# TC264Main.net
KiCad netlist of a schematic drawn in Altium Designer
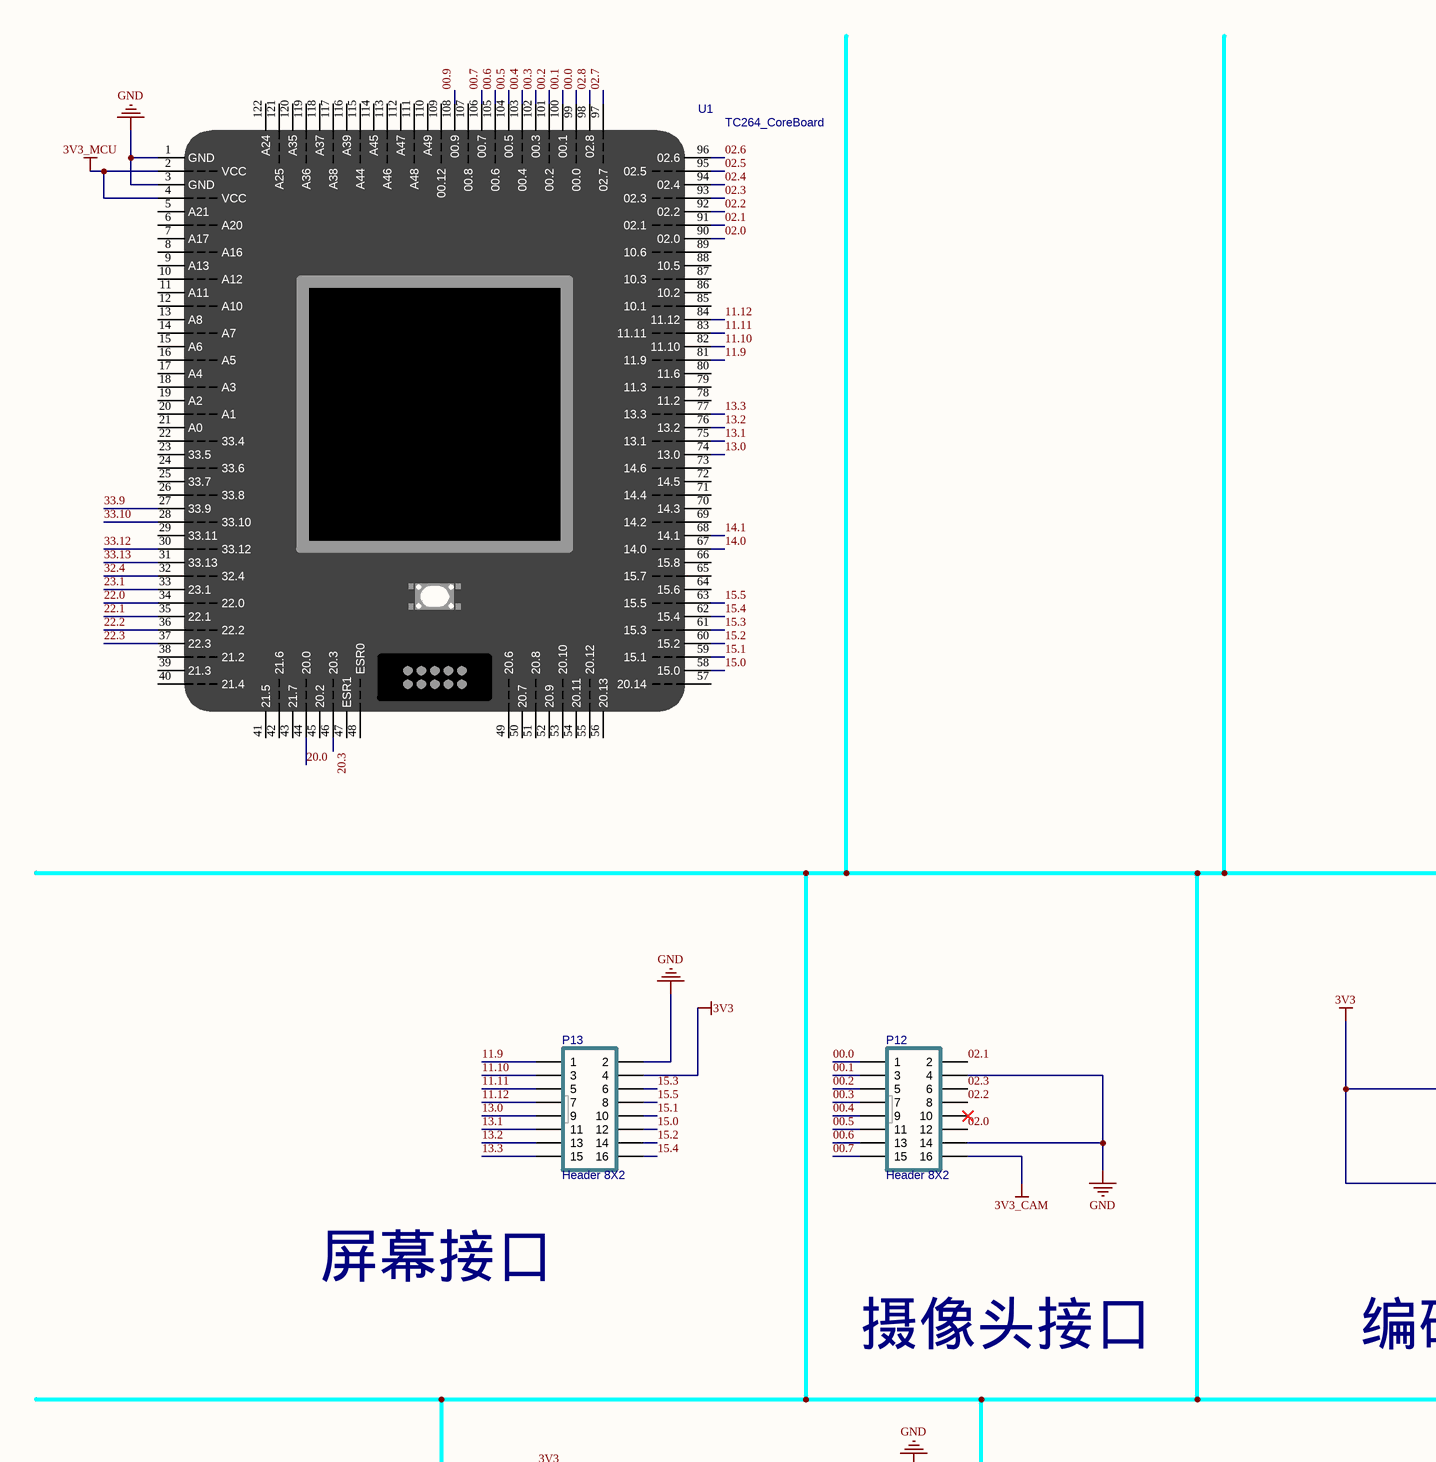
[diagram p0: TC264Main.SchDoc, top left]
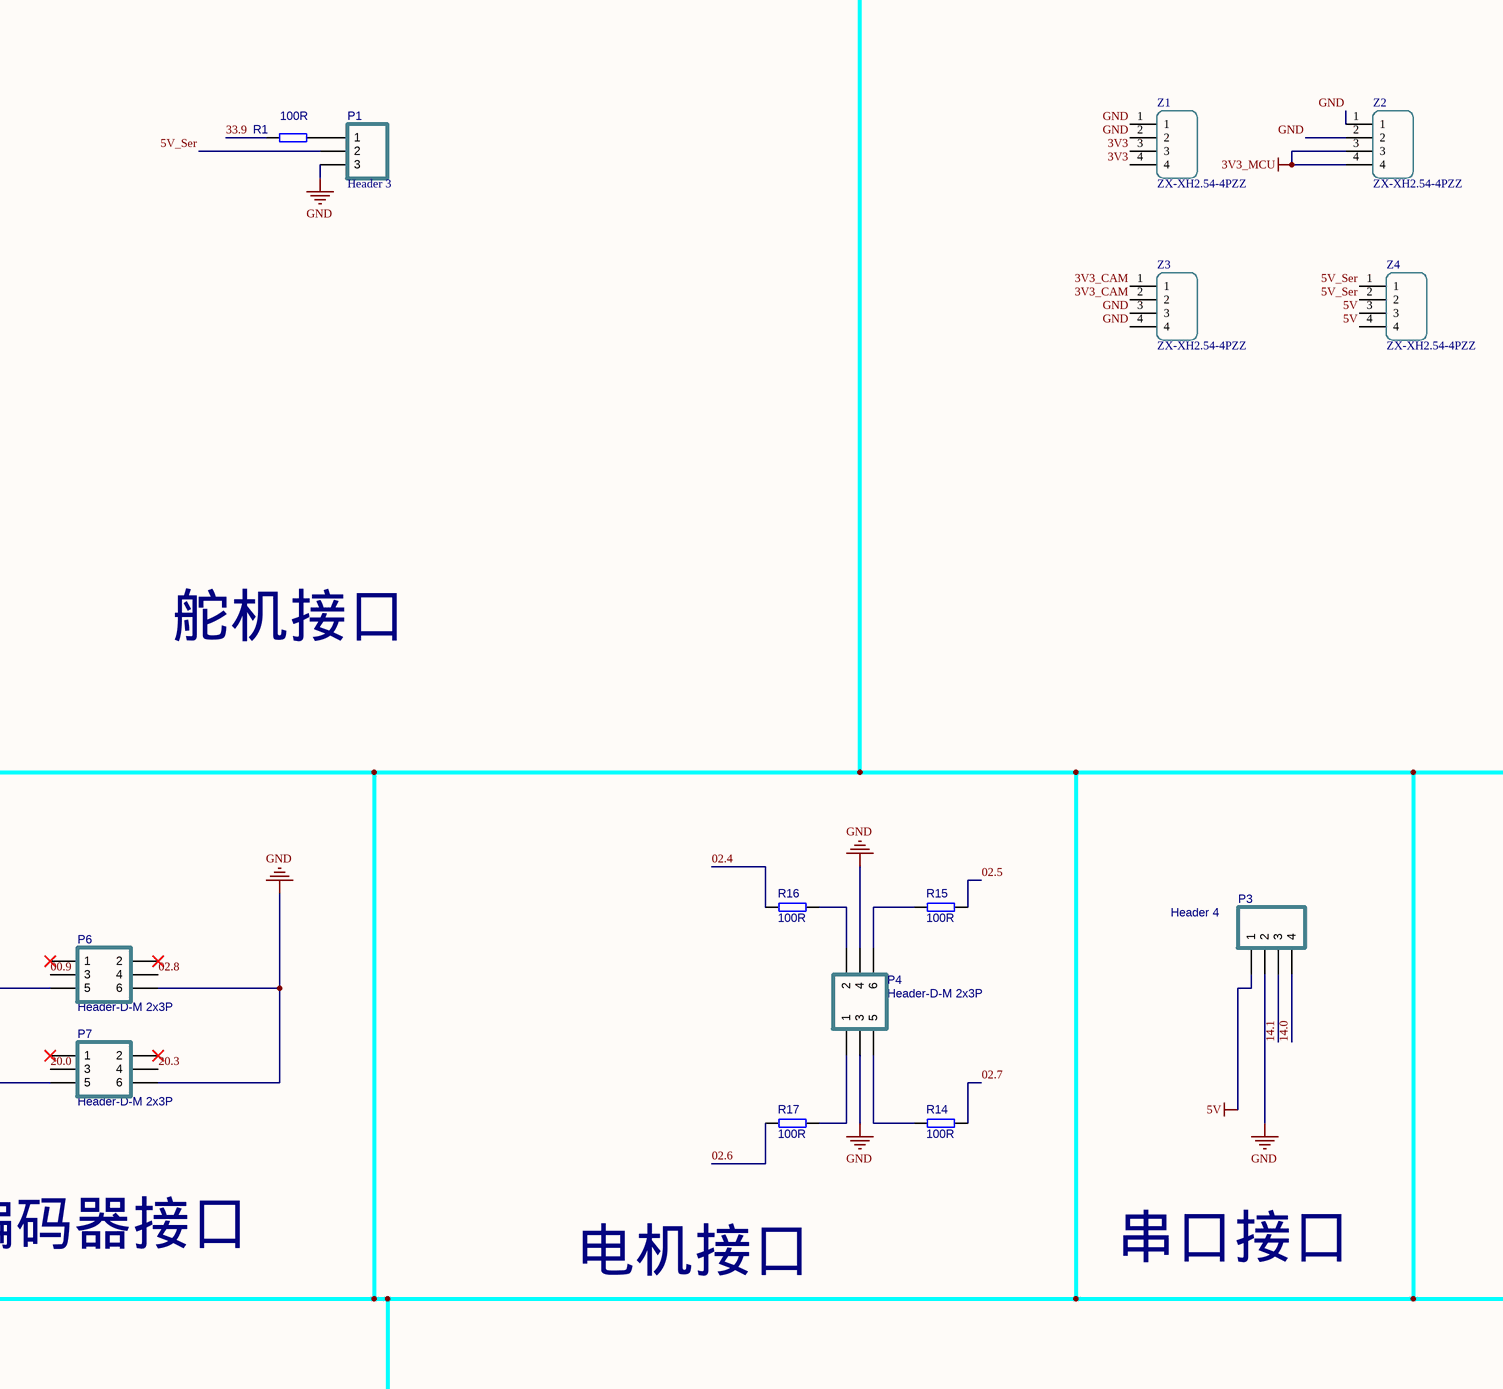
[diagram p1: TC264Main.SchDoc, top middle]
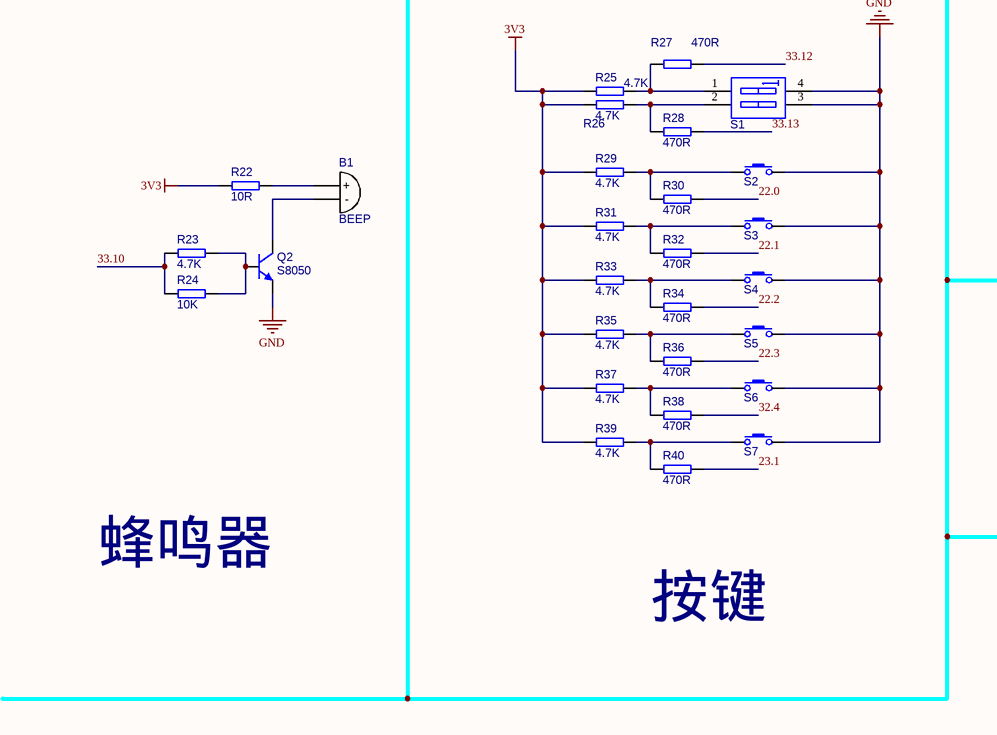
[diagram p2: TC264Main.SchDoc, bottom left]

(export (version "E")
  (design (tool "Eeschema 10.0.6"))
  (components
    (comp (ref "B1")
      (value "BEEP")
      (footprint "BEEP 9x5.5mm")
      (description "蜂鸣器")
      (libsource (lib "TC264") (part "BEEP"))
    )
    (comp (ref "P1")
      (value "Header 3")
      (footprint "HDR1X3")
      (description "Header, 3-Pin")
      (fields (field (name "PUBLISHER") "Altium Limited"))
      (libsource (lib "TC264") (part "Header 3"))
    )
    (comp (ref "P3")
      (value "Header 4")
      (footprint "HDR1X4")
      (description "Header, 4-Pin")
      (fields (field (name "PUBLISHER") "Altium Limited"))
      (libsource (lib "TC264") (part "Header 4"))
    )
    (comp (ref "P4")
      (value "Header-D-M 2x3P")
      (footprint "HDR2X3-M")
      (description "2x3pin, 直插, 双排针")
      (libsource (lib "") (part "Header-D-M 2x3P_1"))
    )
    (comp (ref "P6")
      (value "Header-D-M 2x3P")
      (footprint "HDR2X3-M")
      (description "2x3pin, 直插, 双排针")
      (libsource (lib "TC264") (part "Header-D-M 2x3P"))
    )
    (comp (ref "P7")
      (value "Header-D-M 2x3P")
      (footprint "HDR2X3-M")
      (description "2x3pin, 直插, 双排针")
      (libsource (lib "TC264") (part "Header-D-M 2x3P"))
    )
    (comp (ref "P12")
      (value "Header 8X2")
      (footprint "HDR2X8")
      (description "Header, 8-Pin, Dual row")
      (fields (field (name "PUBLISHER") "Altium Limited"))
      (libsource (lib "TC264") (part "Header 8X2"))
    )
    (comp (ref "P13")
      (value "Header 8X2")
      (footprint "HDR2X8")
      (description "Header, 8-Pin, Dual row")
      (fields (field (name "PUBLISHER") "Altium Limited"))
      (libsource (lib "TC264") (part "Header 8X2"))
    )
    (comp (ref "Q2")
      (value "S8050")
      (footprint "SOT-23")
      (description "Discrete NPN Bipolar Transistor")
      (fields (field (name "PARTNUMBER") "S8050") (field (name "PUBLISHER") "Altium Limited"))
      (libsource (lib "TC264") (part "NPN S8050"))
    )
    (comp (ref "R1")
      (value "100R")
      (footprint "RESC1608[0603]S-N")
      (description "贴片电阻")
      (fields (field (name "TOLERANCE") "±1%") (field (name "Comment") "100R ±1%"))
      (libsource (lib "TC264") (part "Res-Chip_1"))
    )
    (comp (ref "R14")
      (value "100R")
      (footprint "RESC1608[0603]S-N")
      (description "贴片电阻")
      (fields (field (name "TOLERANCE") "±1%") (field (name "Comment") "100R ±1%"))
      (libsource (lib "TC264") (part "Res-Chip_1"))
    )
    (comp (ref "R15")
      (value "100R")
      (footprint "RESC1608[0603]S-N")
      (description "贴片电阻")
      (fields (field (name "TOLERANCE") "±1%") (field (name "Comment") "100R ±1%"))
      (libsource (lib "TC264") (part "Res-Chip_1"))
    )
    (comp (ref "R16")
      (value "100R")
      (footprint "RESC1608[0603]S-N")
      (description "贴片电阻")
      (fields (field (name "TOLERANCE") "±1%") (field (name "Comment") "100R ±1%"))
      (libsource (lib "TC264") (part "Res-Chip_1"))
    )
    (comp (ref "R17")
      (value "100R")
      (footprint "RESC1608[0603]S-N")
      (description "贴片电阻")
      (fields (field (name "TOLERANCE") "±1%") (field (name "Comment") "100R ±1%"))
      (libsource (lib "TC264") (part "Res-Chip_1"))
    )
    (comp (ref "R22")
      (value "10R")
      (footprint "RESC1608[0603]S-N")
      (description "贴片电阻")
      (fields (field (name "TOLERANCE") "±1%") (field (name "Comment") "10R ±1%"))
      (libsource (lib "TC264") (part "Res-Chip_10"))
    )
    (comp (ref "R23")
      (value "4.7K")
      (footprint "RESC1608[0603]S-N")
      (description "贴片电阻")
      (fields (field (name "TOLERANCE") "±1%") (field (name "Comment") "4.7K ±1%"))
      (libsource (lib "TC264") (part "Res-Chip_4"))
    )
    (comp (ref "R24")
      (value "10K")
      (footprint "RESC1608[0603]S-N")
      (description "贴片电阻")
      (fields (field (name "TOLERANCE") "±1%") (field (name "Comment") "10K ±1%"))
      (libsource (lib "TC264") (part "Res-Chip"))
    )
    (comp (ref "R25")
      (value "4.7K")
      (footprint "RESC1608[0603]S-N")
      (description "贴片电阻")
      (fields (field (name "TOLERANCE") "±1%") (field (name "Comment") "4.7K ±1%"))
      (libsource (lib "TC264") (part "Res-Chip_4"))
    )
    (comp (ref "R26")
      (value "4.7K")
      (footprint "RESC1608[0603]S-N")
      (description "贴片电阻")
      (fields (field (name "TOLERANCE") "±1%") (field (name "Comment") "4.7K ±1%"))
      (libsource (lib "TC264") (part "Res-Chip_4"))
    )
    (comp (ref "R27")
      (value "470R")
      (footprint "RESC1608[0603]S-N")
      (description "贴片电阻")
      (fields (field (name "TOLERANCE") "±1%") (field (name "Comment") "470R ±1%"))
      (libsource (lib "TC264") (part "Res-Chip_11"))
    )
    (comp (ref "R28")
      (value "470R")
      (footprint "RESC1608[0603]S-N")
      (description "贴片电阻")
      (fields (field (name "TOLERANCE") "±1%") (field (name "Comment") "470R ±1%"))
      (libsource (lib "TC264") (part "Res-Chip_11"))
    )
    (comp (ref "R29")
      (value "4.7K")
      (footprint "RESC1608[0603]S-N")
      (description "贴片电阻")
      (fields (field (name "TOLERANCE") "±1%") (field (name "Comment") "4.7K ±1%"))
      (libsource (lib "TC264") (part "Res-Chip_4"))
    )
    (comp (ref "R30")
      (value "470R")
      (footprint "RESC1608[0603]S-N")
      (description "贴片电阻")
      (fields (field (name "TOLERANCE") "±1%") (field (name "Comment") "470R ±1%"))
      (libsource (lib "TC264") (part "Res-Chip_11"))
    )
    (comp (ref "R31")
      (value "4.7K")
      (footprint "RESC1608[0603]S-N")
      (description "贴片电阻")
      (fields (field (name "TOLERANCE") "±1%") (field (name "Comment") "4.7K ±1%"))
      (libsource (lib "TC264") (part "Res-Chip_4"))
    )
    (comp (ref "R32")
      (value "470R")
      (footprint "RESC1608[0603]S-N")
      (description "贴片电阻")
      (fields (field (name "TOLERANCE") "±1%") (field (name "Comment") "470R ±1%"))
      (libsource (lib "TC264") (part "Res-Chip_11"))
    )
    (comp (ref "R33")
      (value "4.7K")
      (footprint "RESC1608[0603]S-N")
      (description "贴片电阻")
      (fields (field (name "TOLERANCE") "±1%") (field (name "Comment") "4.7K ±1%"))
      (libsource (lib "TC264") (part "Res-Chip_4"))
    )
    (comp (ref "R34")
      (value "470R")
      (footprint "RESC1608[0603]S-N")
      (description "贴片电阻")
      (fields (field (name "TOLERANCE") "±1%") (field (name "Comment") "470R ±1%"))
      (libsource (lib "TC264") (part "Res-Chip_11"))
    )
    (comp (ref "R35")
      (value "4.7K")
      (footprint "RESC1608[0603]S-N")
      (description "贴片电阻")
      (fields (field (name "TOLERANCE") "±1%") (field (name "Comment") "4.7K ±1%"))
      (libsource (lib "TC264") (part "Res-Chip_4"))
    )
    (comp (ref "R36")
      (value "470R")
      (footprint "RESC1608[0603]S-N")
      (description "贴片电阻")
      (fields (field (name "TOLERANCE") "±1%") (field (name "Comment") "470R ±1%"))
      (libsource (lib "TC264") (part "Res-Chip_11"))
    )
    (comp (ref "R37")
      (value "4.7K")
      (footprint "RESC1608[0603]S-N")
      (description "贴片电阻")
      (fields (field (name "TOLERANCE") "±1%") (field (name "Comment") "4.7K ±1%"))
      (libsource (lib "TC264") (part "Res-Chip_4"))
    )
    (comp (ref "R38")
      (value "470R")
      (footprint "RESC1608[0603]S-N")
      (description "贴片电阻")
      (fields (field (name "TOLERANCE") "±1%") (field (name "Comment") "470R ±1%"))
      (libsource (lib "TC264") (part "Res-Chip_11"))
    )
    (comp (ref "R39")
      (value "4.7K")
      (footprint "RESC1608[0603]S-N")
      (description "贴片电阻")
      (fields (field (name "TOLERANCE") "±1%") (field (name "Comment") "4.7K ±1%"))
      (libsource (lib "TC264") (part "Res-Chip_4"))
    )
    (comp (ref "R40")
      (value "470R")
      (footprint "RESC1608[0603]S-N")
      (description "贴片电阻")
      (fields (field (name "TOLERANCE") "±1%") (field (name "Comment") "470R ±1%"))
      (libsource (lib "TC264") (part "Res-Chip_11"))
    )
    (comp (ref "S1")
      (value "SW DIP-2")
      (footprint "Code SW-2-DIP-2.54")
      (description "2位拨码开关")
      (fields (field (name "PUBLISHER") "Altium Limited"))
      (libsource (lib "TC264") (part "Code SW-2"))
    )
    (comp (ref "S2")
      (value "Button")
      (footprint "PTS810-3*4-CurvePin")
      (description "按键")
      (fields (field (name "PUBLISHER") "Altium Limited"))
      (libsource (lib "TC264") (part "KEY"))
    )
    (comp (ref "S3")
      (value "Button")
      (footprint "PTS810-3*4-CurvePin")
      (description "按键")
      (fields (field (name "PUBLISHER") "Altium Limited"))
      (libsource (lib "TC264") (part "KEY"))
    )
    (comp (ref "S4")
      (value "Button")
      (footprint "PTS810-3*4-CurvePin")
      (description "按键")
      (fields (field (name "PUBLISHER") "Altium Limited"))
      (libsource (lib "TC264") (part "KEY"))
    )
    (comp (ref "S5")
      (value "Button")
      (footprint "PTS810-3*4-CurvePin")
      (description "按键")
      (fields (field (name "PUBLISHER") "Altium Limited"))
      (libsource (lib "TC264") (part "KEY"))
    )
    (comp (ref "S6")
      (value "Button")
      (footprint "PTS810-3*4-CurvePin")
      (description "按键")
      (fields (field (name "PUBLISHER") "Altium Limited"))
      (libsource (lib "TC264") (part "KEY"))
    )
    (comp (ref "S7")
      (value "Button")
      (footprint "PTS810-3*4-CurvePin")
      (description "按键")
      (fields (field (name "PUBLISHER") "Altium Limited"))
      (libsource (lib "TC264") (part "KEY"))
    )
    (comp (ref "U1")
      (value "TC264_CoreBoard")
      (footprint "TC264:TC264_CoreBoard - duplicate")
      (description "逐飞科技TC264核心板")
      (libsource (lib "TC264") (part "TC264_CoreBoard"))
    )
    (comp (ref "Z1")
      (value "ZX-XH2.54-4PZZ")
      (footprint "ZX-XH2.54-4PZZ")
      (description "接线端子")
      (libsource (lib "TangCW") (part "ZX-XH2.54-4PZZ"))
    )
    (comp (ref "Z2")
      (value "ZX-XH2.54-4PZZ")
      (footprint "ZX-XH2.54-4PZZ")
      (description "接线端子")
      (libsource (lib "TangCW") (part "ZX-XH2.54-4PZZ"))
    )
    (comp (ref "Z3")
      (value "ZX-XH2.54-4PZZ")
      (footprint "ZX-XH2.54-4PZZ")
      (description "接线端子")
      (libsource (lib "TangCW") (part "ZX-XH2.54-4PZZ"))
    )
    (comp (ref "Z4")
      (value "ZX-XH2.54-4PZZ")
      (footprint "ZX-XH2.54-4PZZ")
      (description "接线端子")
      (libsource (lib "TangCW") (part "ZX-XH2.54-4PZZ"))
    )
  )
  (nets
    (net (code "1") (name "/00.0") (class "Default")
      (node (ref "P12") (pin "1") (pinfunction "1_1") (pintype "passive"))
      (node (ref "U1") (pin "99") (pinfunction "00.0_99") (pintype "passive"))
    )
    (net (code "2") (name "/00.1") (class "Default")
      (node (ref "P12") (pin "3") (pinfunction "3_3") (pintype "passive"))
      (node (ref "U1") (pin "100") (pinfunction "00.1_100") (pintype "passive"))
    )
    (net (code "3") (name "/00.2") (class "Default")
      (node (ref "P12") (pin "5") (pinfunction "5_5") (pintype "passive"))
      (node (ref "U1") (pin "101") (pinfunction "00.2_101") (pintype "passive"))
    )
    (net (code "4") (name "/00.3") (class "Default")
      (node (ref "P12") (pin "7") (pinfunction "7_7") (pintype "passive"))
      (node (ref "U1") (pin "102") (pinfunction "00.3_102") (pintype "passive"))
    )
    (net (code "5") (name "/00.4") (class "Default")
      (node (ref "P12") (pin "9") (pinfunction "9_9") (pintype "passive"))
      (node (ref "U1") (pin "103") (pinfunction "00.4_103") (pintype "passive"))
    )
    (net (code "6") (name "/00.5") (class "Default")
      (node (ref "P12") (pin "11") (pinfunction "11_11") (pintype "passive"))
      (node (ref "U1") (pin "104") (pinfunction "00.5_104") (pintype "passive"))
    )
    (net (code "7") (name "/00.6") (class "Default")
      (node (ref "P12") (pin "13") (pinfunction "13_13") (pintype "passive"))
      (node (ref "U1") (pin "105") (pinfunction "00.6_105") (pintype "passive"))
    )
    (net (code "8") (name "/00.7") (class "Default")
      (node (ref "P12") (pin "15") (pinfunction "15_15") (pintype "passive"))
      (node (ref "U1") (pin "106") (pinfunction "00.7_106") (pintype "passive"))
    )
    (net (code "9") (name "/00.9") (class "Default")
      (node (ref "P6") (pin "3") (pinfunction "3_3") (pintype "passive"))
      (node (ref "U1") (pin "108") (pinfunction "00.9_108") (pintype "passive"))
    )
    (net (code "10") (name "/02.0") (class "Default")
      (node (ref "P12") (pin "12") (pinfunction "12_12") (pintype "passive"))
      (node (ref "U1") (pin "90") (pinfunction "02.0_90") (pintype "passive"))
    )
    (net (code "11") (name "/02.1") (class "Default")
      (node (ref "P12") (pin "2") (pinfunction "2_2") (pintype "passive"))
      (node (ref "U1") (pin "91") (pinfunction "02.1_91") (pintype "passive"))
    )
    (net (code "12") (name "/02.2") (class "Default")
      (node (ref "P12") (pin "8") (pinfunction "8_8") (pintype "passive"))
      (node (ref "U1") (pin "92") (pinfunction "02.2_92") (pintype "passive"))
    )
    (net (code "13") (name "/02.3") (class "Default")
      (node (ref "P12") (pin "6") (pinfunction "6_6") (pintype "passive"))
      (node (ref "U1") (pin "93") (pinfunction "02.3_93") (pintype "passive"))
    )
    (net (code "14") (name "/02.4") (class "Default")
      (node (ref "R16") (pin "1") (pinfunction "1_1") (pintype "passive"))
      (node (ref "U1") (pin "94") (pinfunction "02.4_94") (pintype "passive"))
    )
    (net (code "15") (name "/02.5") (class "Default")
      (node (ref "R15") (pin "2") (pinfunction "2_2") (pintype "passive"))
      (node (ref "U1") (pin "95") (pinfunction "02.5_95") (pintype "passive"))
    )
    (net (code "16") (name "/02.6") (class "Default")
      (node (ref "R17") (pin "1") (pinfunction "1_1") (pintype "passive"))
      (node (ref "U1") (pin "96") (pinfunction "02.6_96") (pintype "passive"))
    )
    (net (code "17") (name "/02.7") (class "Default")
      (node (ref "R14") (pin "2") (pinfunction "2_2") (pintype "passive"))
      (node (ref "U1") (pin "97") (pinfunction "02.7_97") (pintype "passive"))
    )
    (net (code "18") (name "/02.8") (class "Default")
      (node (ref "P6") (pin "4") (pinfunction "4_4") (pintype "passive"))
      (node (ref "U1") (pin "98") (pinfunction "02.8_98") (pintype "passive"))
    )
    (net (code "19") (name "/5V_Ser") (class "Default")
      (node (ref "P1") (pin "2") (pinfunction "2_2") (pintype "passive"))
      (node (ref "Z4") (pin "1") (pinfunction "1_1") (pintype "passive"))
      (node (ref "Z4") (pin "2") (pinfunction "2_2") (pintype "passive"))
    )
    (net (code "20") (name "/11.9") (class "Default")
      (node (ref "P13") (pin "1") (pinfunction "1_1") (pintype "passive"))
      (node (ref "U1") (pin "81") (pinfunction "11.9_81") (pintype "passive"))
    )
    (net (code "21") (name "/11.10") (class "Default")
      (node (ref "P13") (pin "3") (pinfunction "3_3") (pintype "passive"))
      (node (ref "U1") (pin "82") (pinfunction "11.10_82") (pintype "passive"))
    )
    (net (code "22") (name "/11.11") (class "Default")
      (node (ref "P13") (pin "5") (pinfunction "5_5") (pintype "passive"))
      (node (ref "U1") (pin "83") (pinfunction "11.11_83") (pintype "passive"))
    )
    (net (code "23") (name "/11.12") (class "Default")
      (node (ref "P13") (pin "7") (pinfunction "7_7") (pintype "passive"))
      (node (ref "U1") (pin "84") (pinfunction "11.12_84") (pintype "passive"))
    )
    (net (code "24") (name "/13.0") (class "Default")
      (node (ref "P13") (pin "9") (pinfunction "9_9") (pintype "passive"))
      (node (ref "U1") (pin "74") (pinfunction "13.0_74") (pintype "passive"))
    )
    (net (code "25") (name "/13.1") (class "Default")
      (node (ref "P13") (pin "11") (pinfunction "11_11") (pintype "passive"))
      (node (ref "U1") (pin "75") (pinfunction "13.1_75") (pintype "passive"))
    )
    (net (code "26") (name "/13.2") (class "Default")
      (node (ref "P13") (pin "13") (pinfunction "13_13") (pintype "passive"))
      (node (ref "U1") (pin "76") (pinfunction "13.2_76") (pintype "passive"))
    )
    (net (code "27") (name "/13.3") (class "Default")
      (node (ref "P13") (pin "15") (pinfunction "15_15") (pintype "passive"))
      (node (ref "U1") (pin "77") (pinfunction "13.3_77") (pintype "passive"))
    )
    (net (code "28") (name "/14.0") (class "Default")
      (node (ref "P3") (pin "4") (pinfunction "4_4") (pintype "passive"))
      (node (ref "U1") (pin "67") (pinfunction "14.0_67") (pintype "passive"))
    )
    (net (code "29") (name "/14.1") (class "Default")
      (node (ref "P3") (pin "3") (pinfunction "3_3") (pintype "passive"))
      (node (ref "U1") (pin "68") (pinfunction "14.1_68") (pintype "passive"))
    )
    (net (code "30") (name "/15.0") (class "Default")
      (node (ref "P13") (pin "12") (pinfunction "12_12") (pintype "passive"))
      (node (ref "U1") (pin "58") (pinfunction "15.0_58") (pintype "passive"))
    )
    (net (code "31") (name "/15.1") (class "Default")
      (node (ref "P13") (pin "10") (pinfunction "10_10") (pintype "passive"))
      (node (ref "U1") (pin "59") (pinfunction "15.1_59") (pintype "passive"))
    )
    (net (code "32") (name "/15.2") (class "Default")
      (node (ref "P13") (pin "14") (pinfunction "14_14") (pintype "passive"))
      (node (ref "U1") (pin "60") (pinfunction "15.2_60") (pintype "passive"))
    )
    (net (code "33") (name "/15.3") (class "Default")
      (node (ref "P13") (pin "6") (pinfunction "6_6") (pintype "passive"))
      (node (ref "U1") (pin "61") (pinfunction "15.3_61") (pintype "passive"))
    )
    (net (code "34") (name "/15.4") (class "Default")
      (node (ref "P13") (pin "16") (pinfunction "16_16") (pintype "passive"))
      (node (ref "U1") (pin "62") (pinfunction "15.4_62") (pintype "passive"))
    )
    (net (code "35") (name "/15.5") (class "Default")
      (node (ref "P13") (pin "8") (pinfunction "8_8") (pintype "passive"))
      (node (ref "U1") (pin "63") (pinfunction "15.5_63") (pintype "passive"))
    )
    (net (code "36") (name "/20.0") (class "Default")
      (node (ref "P7") (pin "3") (pinfunction "3_3") (pintype "passive"))
      (node (ref "U1") (pin "44") (pinfunction "20.0_44") (pintype "passive"))
    )
    (net (code "37") (name "/20.3") (class "Default")
      (node (ref "P7") (pin "4") (pinfunction "4_4") (pintype "passive"))
      (node (ref "U1") (pin "46") (pinfunction "20.3_46") (pintype "passive"))
    )
    (net (code "38") (name "/22.0") (class "Default")
      (node (ref "R30") (pin "2") (pinfunction "2_2") (pintype "passive"))
      (node (ref "U1") (pin "34") (pinfunction "22.0_34") (pintype "passive"))
    )
    (net (code "39") (name "/22.1") (class "Default")
      (node (ref "R32") (pin "2") (pinfunction "2_2") (pintype "passive"))
      (node (ref "U1") (pin "35") (pinfunction "22.1_35") (pintype "passive"))
    )
    (net (code "40") (name "/22.2") (class "Default")
      (node (ref "R34") (pin "2") (pinfunction "2_2") (pintype "passive"))
      (node (ref "U1") (pin "36") (pinfunction "22.2_36") (pintype "passive"))
    )
    (net (code "41") (name "/22.3") (class "Default")
      (node (ref "R36") (pin "2") (pinfunction "2_2") (pintype "passive"))
      (node (ref "U1") (pin "37") (pinfunction "22.3_37") (pintype "passive"))
    )
    (net (code "42") (name "/23.1") (class "Default")
      (node (ref "R40") (pin "2") (pinfunction "2_2") (pintype "passive"))
      (node (ref "U1") (pin "33") (pinfunction "23.1_33") (pintype "passive"))
    )
    (net (code "43") (name "/32.4") (class "Default")
      (node (ref "R38") (pin "2") (pinfunction "2_2") (pintype "passive"))
      (node (ref "U1") (pin "32") (pinfunction "32.4_32") (pintype "passive"))
    )
    (net (code "44") (name "/33.9") (class "Default")
      (node (ref "R1") (pin "1") (pinfunction "1_1") (pintype "passive"))
      (node (ref "U1") (pin "27") (pinfunction "33.9_27") (pintype "passive"))
    )
    (net (code "45") (name "/33.10") (class "Default")
      (node (ref "R23") (pin "1") (pinfunction "1_1") (pintype "passive"))
      (node (ref "R24") (pin "1") (pinfunction "1_1") (pintype "passive"))
      (node (ref "U1") (pin "28") (pinfunction "33.10_28") (pintype "passive"))
    )
    (net (code "46") (name "/33.12") (class "Default")
      (node (ref "R27") (pin "2") (pinfunction "2_2") (pintype "passive"))
      (node (ref "U1") (pin "30") (pinfunction "33.12_30") (pintype "passive"))
    )
    (net (code "47") (name "/33.13") (class "Default")
      (node (ref "R28") (pin "2") (pinfunction "2_2") (pintype "passive"))
      (node (ref "U1") (pin "31") (pinfunction "33.13_31") (pintype "passive"))
    )
    (net (code "48") (name "3V3") (class "Default")
      (node (ref "P13") (pin "4") (pinfunction "4_4") (pintype "passive"))
      (node (ref "P6") (pin "5") (pinfunction "5_5") (pintype "passive"))
      (node (ref "P7") (pin "5") (pinfunction "5_5") (pintype "passive"))
      (node (ref "R22") (pin "1") (pinfunction "1_1") (pintype "passive"))
      (node (ref "R25") (pin "1") (pinfunction "1_1") (pintype "passive"))
      (node (ref "R26") (pin "1") (pinfunction "1_1") (pintype "passive"))
      (node (ref "R29") (pin "1") (pinfunction "1_1") (pintype "passive"))
      (node (ref "R31") (pin "1") (pinfunction "1_1") (pintype "passive"))
      (node (ref "R33") (pin "1") (pinfunction "1_1") (pintype "passive"))
      (node (ref "R35") (pin "1") (pinfunction "1_1") (pintype "passive"))
      (node (ref "R37") (pin "1") (pinfunction "1_1") (pintype "passive"))
      (node (ref "R39") (pin "1") (pinfunction "1_1") (pintype "passive"))
      (node (ref "Z1") (pin "3") (pinfunction "3_3") (pintype "passive"))
      (node (ref "Z1") (pin "4") (pinfunction "4_4") (pintype "passive"))
    )
    (net (code "49") (name "3V3_CAM") (class "Default")
      (node (ref "P12") (pin "16") (pinfunction "16_16") (pintype "passive"))
      (node (ref "Z3") (pin "1") (pinfunction "1_1") (pintype "passive"))
      (node (ref "Z3") (pin "2") (pinfunction "2_2") (pintype "passive"))
    )
    (net (code "50") (name "3V3_MCU") (class "Default")
      (node (ref "U1") (pin "2") (pinfunction "VCC_2") (pintype "passive"))
      (node (ref "U1") (pin "4") (pinfunction "VCC_4") (pintype "passive"))
      (node (ref "Z2") (pin "3") (pinfunction "3_3") (pintype "passive"))
      (node (ref "Z2") (pin "4") (pinfunction "4_4") (pintype "passive"))
    )
    (net (code "51") (name "5V") (class "Default")
      (node (ref "P3") (pin "1") (pinfunction "1_1") (pintype "passive"))
      (node (ref "Z4") (pin "3") (pinfunction "3_3") (pintype "passive"))
      (node (ref "Z4") (pin "4") (pinfunction "4_4") (pintype "passive"))
    )
    (net (code "52") (name "GND") (class "Default")
      (node (ref "P1") (pin "3") (pinfunction "3_3") (pintype "passive"))
      (node (ref "P12") (pin "14") (pinfunction "14_14") (pintype "passive"))
      (node (ref "P12") (pin "4") (pinfunction "4_4") (pintype "passive"))
      (node (ref "P13") (pin "2") (pinfunction "2_2") (pintype "passive"))
      (node (ref "P3") (pin "2") (pinfunction "2_2") (pintype "passive"))
      (node (ref "P4") (pin "3") (pinfunction "3_3") (pintype "passive"))
      (node (ref "P4") (pin "4") (pinfunction "4_4") (pintype "passive"))
      (node (ref "P6") (pin "6") (pinfunction "6_6") (pintype "passive"))
      (node (ref "P7") (pin "6") (pinfunction "6_6") (pintype "passive"))
      (node (ref "Q2") (pin "2") (pinfunction "E_2") (pintype "passive"))
      (node (ref "S1") (pin "3") (pinfunction "B2_3") (pintype "passive"))
      (node (ref "S1") (pin "4") (pinfunction "B1_4") (pintype "passive"))
      (node (ref "S2") (pin "1") (pinfunction "1_1") (pintype "passive"))
      (node (ref "S3") (pin "1") (pinfunction "1_1") (pintype "passive"))
      (node (ref "S4") (pin "1") (pinfunction "1_1") (pintype "passive"))
      (node (ref "S5") (pin "1") (pinfunction "1_1") (pintype "passive"))
      (node (ref "S6") (pin "1") (pinfunction "1_1") (pintype "passive"))
      (node (ref "S7") (pin "1") (pinfunction "1_1") (pintype "passive"))
      (node (ref "U1") (pin "1") (pinfunction "GND_1") (pintype "passive"))
      (node (ref "U1") (pin "3") (pinfunction "GND_3") (pintype "passive"))
      (node (ref "Z1") (pin "1") (pinfunction "1_1") (pintype "passive"))
      (node (ref "Z1") (pin "2") (pinfunction "2_2") (pintype "passive"))
      (node (ref "Z2") (pin "1") (pinfunction "1_1") (pintype "passive"))
      (node (ref "Z2") (pin "2") (pinfunction "2_2") (pintype "passive"))
      (node (ref "Z3") (pin "3") (pinfunction "3_3") (pintype "passive"))
      (node (ref "Z3") (pin "4") (pinfunction "4_4") (pintype "passive"))
    )
    (net (code "53") (name "Net-(B1-+)") (class "Default")
      (node (ref "B1") (pin "1") (pinfunction "+_1") (pintype "passive"))
      (node (ref "R22") (pin "2") (pinfunction "2_2") (pintype "passive"))
    )
    (net (code "54") (name "Net-(B1--)") (class "Default")
      (node (ref "B1") (pin "2") (pinfunction "-_2") (pintype "passive"))
      (node (ref "Q2") (pin "3") (pinfunction "C_3") (pintype "passive"))
    )
    (net (code "55") (name "Net-(P1-Pad1)") (class "Default")
      (node (ref "P1") (pin "1") (pinfunction "1_1") (pintype "passive"))
      (node (ref "R1") (pin "2") (pinfunction "2_2") (pintype "passive"))
    )
    (net (code "56") (name "Net-(P4-Pad1)") (class "Default")
      (node (ref "P4") (pin "1") (pinfunction "1_1") (pintype "passive"))
      (node (ref "R17") (pin "2") (pinfunction "2_2") (pintype "passive"))
    )
    (net (code "57") (name "Net-(P4-Pad2)") (class "Default")
      (node (ref "P4") (pin "2") (pinfunction "2_2") (pintype "passive"))
      (node (ref "R16") (pin "2") (pinfunction "2_2") (pintype "passive"))
    )
    (net (code "58") (name "Net-(P4-Pad5)") (class "Default")
      (node (ref "P4") (pin "5") (pinfunction "5_5") (pintype "passive"))
      (node (ref "R14") (pin "1") (pinfunction "1_1") (pintype "passive"))
    )
    (net (code "59") (name "Net-(P4-Pad6)") (class "Default")
      (node (ref "P4") (pin "6") (pinfunction "6_6") (pintype "passive"))
      (node (ref "R15") (pin "1") (pinfunction "1_1") (pintype "passive"))
    )
    (net (code "60") (name "Net-(Q2-B)") (class "Default")
      (node (ref "Q2") (pin "1") (pinfunction "B_1") (pintype "passive"))
      (node (ref "R23") (pin "2") (pinfunction "2_2") (pintype "passive"))
      (node (ref "R24") (pin "2") (pinfunction "2_2") (pintype "passive"))
    )
    (net (code "61") (name "Net-(R29-Pad2)") (class "Default")
      (node (ref "R29") (pin "2") (pinfunction "2_2") (pintype "passive"))
      (node (ref "R30") (pin "1") (pinfunction "1_1") (pintype "passive"))
      (node (ref "S2") (pin "2") (pinfunction "2_2") (pintype "passive"))
    )
    (net (code "62") (name "Net-(R31-Pad2)") (class "Default")
      (node (ref "R31") (pin "2") (pinfunction "2_2") (pintype "passive"))
      (node (ref "R32") (pin "1") (pinfunction "1_1") (pintype "passive"))
      (node (ref "S3") (pin "2") (pinfunction "2_2") (pintype "passive"))
    )
    (net (code "63") (name "Net-(R33-Pad2)") (class "Default")
      (node (ref "R33") (pin "2") (pinfunction "2_2") (pintype "passive"))
      (node (ref "R34") (pin "1") (pinfunction "1_1") (pintype "passive"))
      (node (ref "S4") (pin "2") (pinfunction "2_2") (pintype "passive"))
    )
    (net (code "64") (name "Net-(R35-Pad2)") (class "Default")
      (node (ref "R35") (pin "2") (pinfunction "2_2") (pintype "passive"))
      (node (ref "R36") (pin "1") (pinfunction "1_1") (pintype "passive"))
      (node (ref "S5") (pin "2") (pinfunction "2_2") (pintype "passive"))
    )
    (net (code "65") (name "Net-(R37-Pad2)") (class "Default")
      (node (ref "R37") (pin "2") (pinfunction "2_2") (pintype "passive"))
      (node (ref "R38") (pin "1") (pinfunction "1_1") (pintype "passive"))
      (node (ref "S6") (pin "2") (pinfunction "2_2") (pintype "passive"))
    )
    (net (code "66") (name "Net-(R39-Pad2)") (class "Default")
      (node (ref "R39") (pin "2") (pinfunction "2_2") (pintype "passive"))
      (node (ref "R40") (pin "1") (pinfunction "1_1") (pintype "passive"))
      (node (ref "S7") (pin "2") (pinfunction "2_2") (pintype "passive"))
    )
    (net (code "67") (name "Net-(S1-A1)") (class "Default")
      (node (ref "R25") (pin "2") (pinfunction "2_2") (pintype "passive"))
      (node (ref "R27") (pin "1") (pinfunction "1_1") (pintype "passive"))
      (node (ref "S1") (pin "1") (pinfunction "A1_1") (pintype "passive"))
    )
    (net (code "68") (name "Net-(S1-A2)") (class "Default")
      (node (ref "R26") (pin "2") (pinfunction "2_2") (pintype "passive"))
      (node (ref "R28") (pin "1") (pinfunction "1_1") (pintype "passive"))
      (node (ref "S1") (pin "2") (pinfunction "A2_2") (pintype "passive"))
    )
    (net (code "69") (name "unconnected-(P6-Pad1)") (class "Default")
      (node (ref "P6") (pin "1") (pinfunction "1_1") (pintype "passive+no_connect"))
    )
    (net (code "70") (name "unconnected-(P6-Pad2)") (class "Default")
      (node (ref "P6") (pin "2") (pinfunction "2_2") (pintype "passive+no_connect"))
    )
    (net (code "71") (name "unconnected-(P7-Pad1)") (class "Default")
      (node (ref "P7") (pin "1") (pinfunction "1_1") (pintype "passive+no_connect"))
    )
    (net (code "72") (name "unconnected-(P7-Pad2)") (class "Default")
      (node (ref "P7") (pin "2") (pinfunction "2_2") (pintype "passive+no_connect"))
    )
    (net (code "73") (name "unconnected-(P12-Pad10)") (class "Default")
      (node (ref "P12") (pin "10") (pinfunction "10_10") (pintype "passive+no_connect"))
    )
    (net (code "74") (name "unconnected-(U1-00.8-Pad107)") (class "Default")
      (node (ref "U1") (pin "107") (pinfunction "00.8_107") (pintype "passive"))
    )
    (net (code "75") (name "unconnected-(U1-00.12-Pad109)") (class "Default")
      (node (ref "U1") (pin "109") (pinfunction "00.12_109") (pintype "passive"))
    )
    (net (code "76") (name "unconnected-(U1-10.1-Pad85)") (class "Default")
      (node (ref "U1") (pin "85") (pinfunction "10.1_85") (pintype "passive"))
    )
    (net (code "77") (name "unconnected-(U1-10.2-Pad86)") (class "Default")
      (node (ref "U1") (pin "86") (pinfunction "10.2_86") (pintype "passive"))
    )
    (net (code "78") (name "unconnected-(U1-10.3-Pad87)") (class "Default")
      (node (ref "U1") (pin "87") (pinfunction "10.3_87") (pintype "passive"))
    )
    (net (code "79") (name "unconnected-(U1-10.5-Pad88)") (class "Default")
      (node (ref "U1") (pin "88") (pinfunction "10.5_88") (pintype "passive"))
    )
    (net (code "80") (name "unconnected-(U1-10.6-Pad89)") (class "Default")
      (node (ref "U1") (pin "89") (pinfunction "10.6_89") (pintype "passive"))
    )
    (net (code "81") (name "unconnected-(U1-11.2-Pad78)") (class "Default")
      (node (ref "U1") (pin "78") (pinfunction "11.2_78") (pintype "passive"))
    )
    (net (code "82") (name "unconnected-(U1-11.3-Pad79)") (class "Default")
      (node (ref "U1") (pin "79") (pinfunction "11.3_79") (pintype "passive"))
    )
    (net (code "83") (name "unconnected-(U1-11.6-Pad80)") (class "Default")
      (node (ref "U1") (pin "80") (pinfunction "11.6_80") (pintype "passive"))
    )
    (net (code "84") (name "unconnected-(U1-14.2-Pad69)") (class "Default")
      (node (ref "U1") (pin "69") (pinfunction "14.2_69") (pintype "passive"))
    )
    (net (code "85") (name "unconnected-(U1-14.3-Pad70)") (class "Default")
      (node (ref "U1") (pin "70") (pinfunction "14.3_70") (pintype "passive"))
    )
    (net (code "86") (name "unconnected-(U1-14.4-Pad71)") (class "Default")
      (node (ref "U1") (pin "71") (pinfunction "14.4_71") (pintype "passive"))
    )
    (net (code "87") (name "unconnected-(U1-14.5-Pad72)") (class "Default")
      (node (ref "U1") (pin "72") (pinfunction "14.5_72") (pintype "passive"))
    )
    (net (code "88") (name "unconnected-(U1-14.6-Pad73)") (class "Default")
      (node (ref "U1") (pin "73") (pinfunction "14.6_73") (pintype "passive"))
    )
    (net (code "89") (name "unconnected-(U1-15.6-Pad64)") (class "Default")
      (node (ref "U1") (pin "64") (pinfunction "15.6_64") (pintype "passive"))
    )
    (net (code "90") (name "unconnected-(U1-15.7-Pad65)") (class "Default")
      (node (ref "U1") (pin "65") (pinfunction "15.7_65") (pintype "passive"))
    )
    (net (code "91") (name "unconnected-(U1-15.8-Pad66)") (class "Default")
      (node (ref "U1") (pin "66") (pinfunction "15.8_66") (pintype "passive"))
    )
    (net (code "92") (name "unconnected-(U1-20.2-Pad45)") (class "Default")
      (node (ref "U1") (pin "45") (pinfunction "20.2_45") (pintype "passive"))
    )
    (net (code "93") (name "unconnected-(U1-20.6-Pad49)") (class "Default")
      (node (ref "U1") (pin "49") (pinfunction "20.6_49") (pintype "passive"))
    )
    (net (code "94") (name "unconnected-(U1-20.7-Pad50)") (class "Default")
      (node (ref "U1") (pin "50") (pinfunction "20.7_50") (pintype "passive"))
    )
    (net (code "95") (name "unconnected-(U1-20.8-Pad51)") (class "Default")
      (node (ref "U1") (pin "51") (pinfunction "20.8_51") (pintype "passive"))
    )
    (net (code "96") (name "unconnected-(U1-20.9-Pad52)") (class "Default")
      (node (ref "U1") (pin "52") (pinfunction "20.9_52") (pintype "passive"))
    )
    (net (code "97") (name "unconnected-(U1-20.10-Pad53)") (class "Default")
      (node (ref "U1") (pin "53") (pinfunction "20.10_53") (pintype "passive"))
    )
    (net (code "98") (name "unconnected-(U1-20.11-Pad54)") (class "Default")
      (node (ref "U1") (pin "54") (pinfunction "20.11_54") (pintype "passive"))
    )
    (net (code "99") (name "unconnected-(U1-20.12-Pad55)") (class "Default")
      (node (ref "U1") (pin "55") (pinfunction "20.12_55") (pintype "passive"))
    )
    (net (code "100") (name "unconnected-(U1-20.13-Pad56)") (class "Default")
      (node (ref "U1") (pin "56") (pinfunction "20.13_56") (pintype "passive"))
    )
    (net (code "101") (name "unconnected-(U1-20.14-Pad57)") (class "Default")
      (node (ref "U1") (pin "57") (pinfunction "20.14_57") (pintype "passive"))
    )
    (net (code "102") (name "unconnected-(U1-21.2-Pad38)") (class "Default")
      (node (ref "U1") (pin "38") (pinfunction "21.2_38") (pintype "passive"))
    )
    (net (code "103") (name "unconnected-(U1-21.3-Pad39)") (class "Default")
      (node (ref "U1") (pin "39") (pinfunction "21.3_39") (pintype "passive"))
    )
    (net (code "104") (name "unconnected-(U1-21.4-Pad40)") (class "Default")
      (node (ref "U1") (pin "40") (pinfunction "21.4_40") (pintype "passive"))
    )
    (net (code "105") (name "unconnected-(U1-21.5-Pad41)") (class "Default")
      (node (ref "U1") (pin "41") (pinfunction "21.5_41") (pintype "passive"))
    )
    (net (code "106") (name "unconnected-(U1-21.6-Pad42)") (class "Default")
      (node (ref "U1") (pin "42") (pinfunction "21.6_42") (pintype "passive"))
    )
    (net (code "107") (name "unconnected-(U1-21.7-Pad43)") (class "Default")
      (node (ref "U1") (pin "43") (pinfunction "21.7_43") (pintype "passive"))
    )
    (net (code "108") (name "unconnected-(U1-33.4-Pad22)") (class "Default")
      (node (ref "U1") (pin "22") (pinfunction "33.4_22") (pintype "passive"))
    )
    (net (code "109") (name "unconnected-(U1-33.5-Pad23)") (class "Default")
      (node (ref "U1") (pin "23") (pinfunction "33.5_23") (pintype "passive"))
    )
    (net (code "110") (name "unconnected-(U1-33.6-Pad24)") (class "Default")
      (node (ref "U1") (pin "24") (pinfunction "33.6_24") (pintype "passive"))
    )
    (net (code "111") (name "unconnected-(U1-33.7-Pad25)") (class "Default")
      (node (ref "U1") (pin "25") (pinfunction "33.7_25") (pintype "passive"))
    )
    (net (code "112") (name "unconnected-(U1-33.8-Pad26)") (class "Default")
      (node (ref "U1") (pin "26") (pinfunction "33.8_26") (pintype "passive"))
    )
    (net (code "113") (name "unconnected-(U1-33.11-Pad29)") (class "Default")
      (node (ref "U1") (pin "29") (pinfunction "33.11_29") (pintype "passive"))
    )
    (net (code "114") (name "unconnected-(U1-A0-Pad21)") (class "Default")
      (node (ref "U1") (pin "21") (pinfunction "A0_21") (pintype "passive"))
    )
    (net (code "115") (name "unconnected-(U1-A1-Pad20)") (class "Default")
      (node (ref "U1") (pin "20") (pinfunction "A1_20") (pintype "passive"))
    )
    (net (code "116") (name "unconnected-(U1-A2-Pad19)") (class "Default")
      (node (ref "U1") (pin "19") (pinfunction "A2_19") (pintype "passive"))
    )
    (net (code "117") (name "unconnected-(U1-A3-Pad18)") (class "Default")
      (node (ref "U1") (pin "18") (pinfunction "A3_18") (pintype "passive"))
    )
    (net (code "118") (name "unconnected-(U1-A4-Pad17)") (class "Default")
      (node (ref "U1") (pin "17") (pinfunction "A4_17") (pintype "passive"))
    )
    (net (code "119") (name "unconnected-(U1-A5-Pad16)") (class "Default")
      (node (ref "U1") (pin "16") (pinfunction "A5_16") (pintype "passive"))
    )
    (net (code "120") (name "unconnected-(U1-A6-Pad15)") (class "Default")
      (node (ref "U1") (pin "15") (pinfunction "A6_15") (pintype "passive"))
    )
    (net (code "121") (name "unconnected-(U1-A7-Pad14)") (class "Default")
      (node (ref "U1") (pin "14") (pinfunction "A7_14") (pintype "passive"))
    )
    (net (code "122") (name "unconnected-(U1-A8-Pad13)") (class "Default")
      (node (ref "U1") (pin "13") (pinfunction "A8_13") (pintype "passive"))
    )
    (net (code "123") (name "unconnected-(U1-A10-Pad12)") (class "Default")
      (node (ref "U1") (pin "12") (pinfunction "A10_12") (pintype "passive"))
    )
    (net (code "124") (name "unconnected-(U1-A11-Pad11)") (class "Default")
      (node (ref "U1") (pin "11") (pinfunction "A11_11") (pintype "passive"))
    )
    (net (code "125") (name "unconnected-(U1-A12-Pad10)") (class "Default")
      (node (ref "U1") (pin "10") (pinfunction "A12_10") (pintype "passive"))
    )
    (net (code "126") (name "unconnected-(U1-A13-Pad9)") (class "Default")
      (node (ref "U1") (pin "9") (pinfunction "A13_9") (pintype "passive"))
    )
    (net (code "127") (name "unconnected-(U1-A16-Pad8)") (class "Default")
      (node (ref "U1") (pin "8") (pinfunction "A16_8") (pintype "passive"))
    )
    (net (code "128") (name "unconnected-(U1-A17-Pad7)") (class "Default")
      (node (ref "U1") (pin "7") (pinfunction "A17_7") (pintype "passive"))
    )
    (net (code "129") (name "unconnected-(U1-A20-Pad6)") (class "Default")
      (node (ref "U1") (pin "6") (pinfunction "A20_6") (pintype "passive"))
    )
    (net (code "130") (name "unconnected-(U1-A21-Pad5)") (class "Default")
      (node (ref "U1") (pin "5") (pinfunction "A21_5") (pintype "passive"))
    )
    (net (code "131") (name "unconnected-(U1-A24-Pad122)") (class "Default")
      (node (ref "U1") (pin "122") (pinfunction "A24_122") (pintype "passive"))
    )
    (net (code "132") (name "unconnected-(U1-A25-Pad121)") (class "Default")
      (node (ref "U1") (pin "121") (pinfunction "A25_121") (pintype "passive"))
    )
    (net (code "133") (name "unconnected-(U1-A35-Pad120)") (class "Default")
      (node (ref "U1") (pin "120") (pinfunction "A35_120") (pintype "passive"))
    )
    (net (code "134") (name "unconnected-(U1-A36-Pad119)") (class "Default")
      (node (ref "U1") (pin "119") (pinfunction "A36_119") (pintype "passive"))
    )
    (net (code "135") (name "unconnected-(U1-A37-Pad118)") (class "Default")
      (node (ref "U1") (pin "118") (pinfunction "A37_118") (pintype "passive"))
    )
    (net (code "136") (name "unconnected-(U1-A38-Pad117)") (class "Default")
      (node (ref "U1") (pin "117") (pinfunction "A38_117") (pintype "passive"))
    )
    (net (code "137") (name "unconnected-(U1-A39-Pad116)") (class "Default")
      (node (ref "U1") (pin "116") (pinfunction "A39_116") (pintype "passive"))
    )
    (net (code "138") (name "unconnected-(U1-A44-Pad115)") (class "Default")
      (node (ref "U1") (pin "115") (pinfunction "A44_115") (pintype "passive"))
    )
    (net (code "139") (name "unconnected-(U1-A45-Pad114)") (class "Default")
      (node (ref "U1") (pin "114") (pinfunction "A45_114") (pintype "passive"))
    )
    (net (code "140") (name "unconnected-(U1-A46-Pad113)") (class "Default")
      (node (ref "U1") (pin "113") (pinfunction "A46_113") (pintype "passive"))
    )
    (net (code "141") (name "unconnected-(U1-A47-Pad112)") (class "Default")
      (node (ref "U1") (pin "112") (pinfunction "A47_112") (pintype "passive"))
    )
    (net (code "142") (name "unconnected-(U1-A48-Pad111)") (class "Default")
      (node (ref "U1") (pin "111") (pinfunction "A48_111") (pintype "passive"))
    )
    (net (code "143") (name "unconnected-(U1-A49-Pad110)") (class "Default")
      (node (ref "U1") (pin "110") (pinfunction "A49_110") (pintype "passive"))
    )
    (net (code "144") (name "unconnected-(U1-ESR0-Pad48)") (class "Default")
      (node (ref "U1") (pin "48") (pinfunction "ESR0_48") (pintype "passive"))
    )
    (net (code "145") (name "unconnected-(U1-ESR1-Pad47)") (class "Default")
      (node (ref "U1") (pin "47") (pinfunction "ESR1_47") (pintype "passive"))
    )
  )
)
